# MotorController.net
KiCad netlist of a schematic drawn in EAGLE
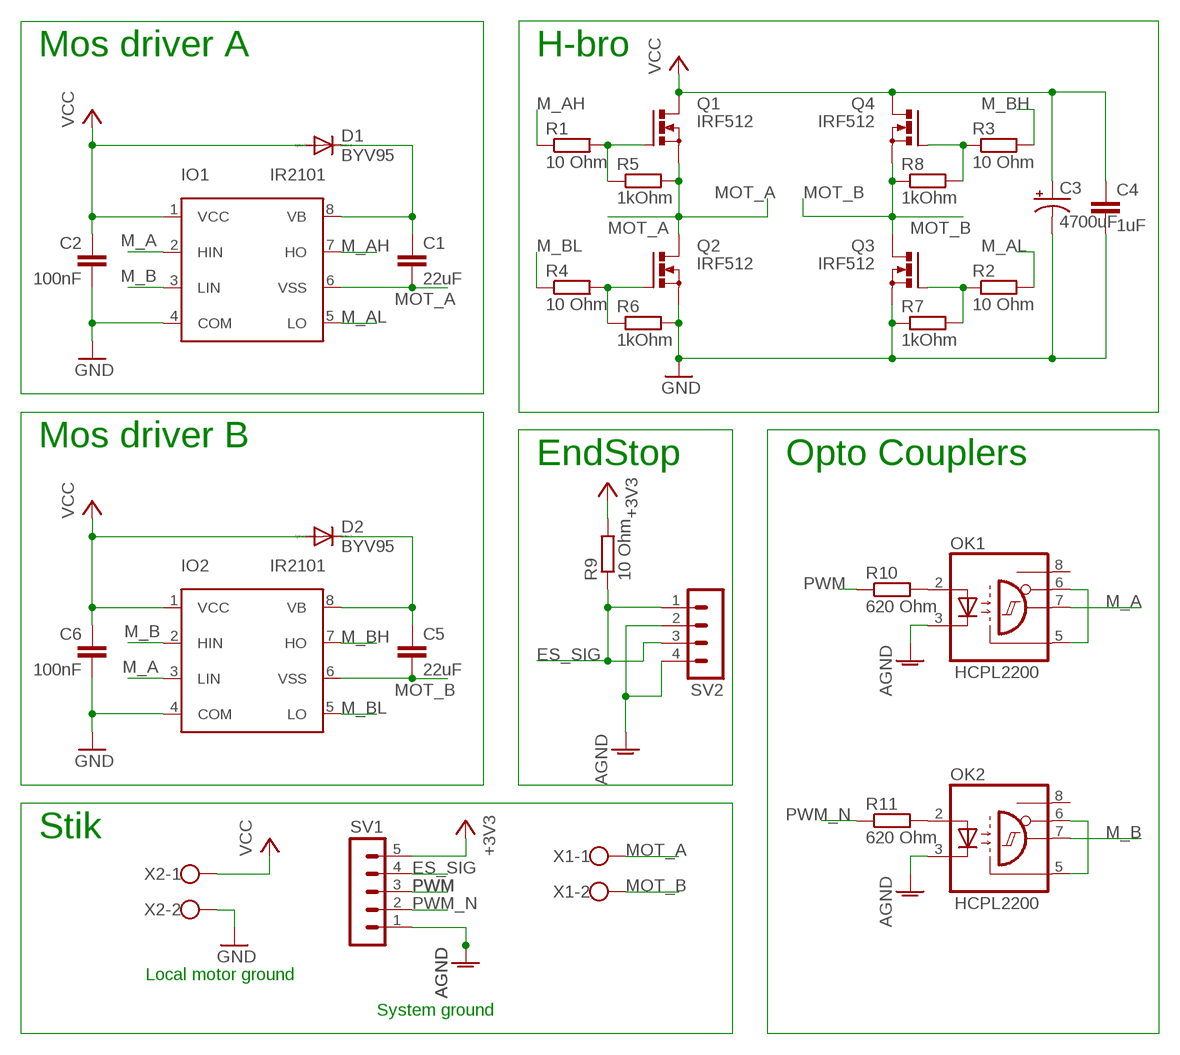
[diagram p0: schematic, sheet 1]

(export (version "E")
  (design (tool "Eeschema 10.0.6"))
  (components
    (comp (ref "C1")
      (value "22uF")
      (footprint "eagle-import:CAP-PTH-5MM")
      (libsource (lib "eagle-import") (part "CAPPTH1"))
    )
    (comp (ref "C2")
      (value "100nF")
      (footprint "eagle-import:CAP-PTH-5MM")
      (libsource (lib "eagle-import") (part "CAPPTH1"))
    )
    (comp (ref "C3")
      (value "4700uF")
      (footprint "eagle-import:CPOL-RADIAL-1000UF-25V")
      (libsource (lib "eagle-import") (part "CAP_POLPTH4"))
    )
    (comp (ref "C4")
      (value "1uF")
      (footprint "eagle-import:CAP-PTH-5MM")
      (libsource (lib "eagle-import") (part "CAPPTH1"))
    )
    (comp (ref "C5")
      (value "22uF")
      (footprint "eagle-import:CAP-PTH-5MM")
      (libsource (lib "eagle-import") (part "CAPPTH1"))
    )
    (comp (ref "C6")
      (value "100nF")
      (footprint "eagle-import:CAP-PTH-5MM")
      (libsource (lib "eagle-import") (part "CAPPTH1"))
    )
    (comp (ref "D1")
      (value "BYV95")
      (footprint "eagle-import:SOD57-10")
      (libsource (lib "eagle-import") (part "BYV95"))
    )
    (comp (ref "D2")
      (value "BYV95")
      (footprint "eagle-import:SOD57-10")
      (libsource (lib "eagle-import") (part "BYV95"))
    )
    (comp (ref "IO1")
      (value "IR2101")
      (footprint "eagle-import:DIL08")
      (libsource (lib "eagle-import") (part "IR2101"))
    )
    (comp (ref "IO2")
      (value "IR2101")
      (footprint "eagle-import:DIL08")
      (libsource (lib "eagle-import") (part "IR2101"))
    )
    (comp (ref "OK1")
      (value "HCPL2200")
      (footprint "eagle-import:DIL08")
      (fields (field (name "MF") "AGILENT TECHNOLOGIES") (field (name "MPN") "HCPL-2200"))
      (libsource (lib "eagle-import") (part "HCPL2200"))
    )
    (comp (ref "OK2")
      (value "HCPL2200")
      (footprint "eagle-import:DIL08")
      (fields (field (name "MF") "AGILENT TECHNOLOGIES") (field (name "MPN") "HCPL-2200"))
      (libsource (lib "eagle-import") (part "HCPL2200"))
    )
    (comp (ref "Q1")
      (value "IRF512")
      (footprint "eagle-import:TO220BV")
      (libsource (lib "eagle-import") (part "IRF512"))
    )
    (comp (ref "Q2")
      (value "IRF512")
      (footprint "eagle-import:TO220BV")
      (libsource (lib "eagle-import") (part "IRF512"))
    )
    (comp (ref "Q3")
      (value "IRF512")
      (footprint "eagle-import:TO220BV")
      (libsource (lib "eagle-import") (part "IRF512"))
    )
    (comp (ref "Q4")
      (value "IRF512")
      (footprint "eagle-import:TO220BV")
      (libsource (lib "eagle-import") (part "IRF512"))
    )
    (comp (ref "R1")
      (value "10 Ohm")
      (footprint "eagle-import:0207_10")
      (libsource (lib "eagle-import") (part "R-EU_0207/10"))
    )
    (comp (ref "R2")
      (value "10 Ohm")
      (footprint "eagle-import:0207_10")
      (libsource (lib "eagle-import") (part "R-EU_0207/10"))
    )
    (comp (ref "R3")
      (value "10 Ohm")
      (footprint "eagle-import:0207_10")
      (libsource (lib "eagle-import") (part "R-EU_0207/10"))
    )
    (comp (ref "R4")
      (value "10 Ohm")
      (footprint "eagle-import:0207_10")
      (libsource (lib "eagle-import") (part "R-EU_0207/10"))
    )
    (comp (ref "R5")
      (value "1kOhm")
      (footprint "eagle-import:0207_10")
      (libsource (lib "eagle-import") (part "R-EU_0207/10"))
    )
    (comp (ref "R6")
      (value "1kOhm")
      (footprint "eagle-import:0207_10")
      (libsource (lib "eagle-import") (part "R-EU_0207/10"))
    )
    (comp (ref "R7")
      (value "1kOhm")
      (footprint "eagle-import:0207_10")
      (libsource (lib "eagle-import") (part "R-EU_0207/10"))
    )
    (comp (ref "R8")
      (value "1kOhm")
      (footprint "eagle-import:0207_10")
      (libsource (lib "eagle-import") (part "R-EU_0207/10"))
    )
    (comp (ref "R9")
      (value "10 Ohm")
      (footprint "eagle-import:0207_10")
      (libsource (lib "eagle-import") (part "R-EU_0207/10"))
    )
    (comp (ref "R10")
      (value "620 Ohm")
      (footprint "eagle-import:0207_10")
      (libsource (lib "eagle-import") (part "R-EU_0207/10"))
    )
    (comp (ref "R11")
      (value "620 Ohm")
      (footprint "eagle-import:0207_10")
      (libsource (lib "eagle-import") (part "R-EU_0207/10"))
    )
    (comp (ref "SV1")
      (value "MA05-1")
      (footprint "eagle-import:MA05-1")
      (libsource (lib "eagle-import") (part "MA05-1"))
    )
    (comp (ref "SV2")
      (value "MA04-1")
      (footprint "eagle-import:MA04-1")
      (libsource (lib "eagle-import") (part "MA04-1"))
    )
    (comp (ref "X1")
      (value "W237-102")
      (footprint "eagle-import:W237-102")
      (fields (field (name "MPN") "237-102"))
      (libsource (lib "eagle-import") (part "W237-102"))
    )
    (comp (ref "X2")
      (value "W237-102")
      (footprint "eagle-import:W237-102")
      (fields (field (name "MPN") "237-102"))
      (libsource (lib "eagle-import") (part "W237-102"))
    )
  )
  (nets
    (net (code "1") (name "+3V3") (class "Default")
      (node (ref "R9") (pin "2") (pinfunction "2_2") (pintype "passive"))
      (node (ref "SV1") (pin "5") (pinfunction "5_5") (pintype "passive"))
    )
    (net (code "2") (name "/ES_SIG") (class "Default")
      (node (ref "R9") (pin "1") (pinfunction "1_1") (pintype "passive"))
      (node (ref "SV1") (pin "4") (pinfunction "4_4") (pintype "passive"))
      (node (ref "SV2") (pin "1") (pinfunction "1_1") (pintype "passive"))
      (node (ref "SV2") (pin "3") (pinfunction "3_3") (pintype "passive"))
    )
    (net (code "3") (name "/MOT_A") (class "Default")
      (node (ref "C1") (pin "2") (pinfunction "2_2") (pintype "passive"))
      (node (ref "IO1") (pin "6") (pinfunction "VSS_6") (pintype "bidirectional"))
      (node (ref "Q1") (pin "S") (pinfunction "S_S") (pintype "passive"))
      (node (ref "Q2") (pin "D") (pinfunction "D_D") (pintype "passive"))
      (node (ref "R5") (pin "2") (pinfunction "2_2") (pintype "passive"))
      (node (ref "X1") (pin "1") (pinfunction "KL_1") (pintype "passive"))
    )
    (net (code "4") (name "/MOT_B") (class "Default")
      (node (ref "C5") (pin "2") (pinfunction "2_2") (pintype "passive"))
      (node (ref "IO2") (pin "6") (pinfunction "VSS_6") (pintype "bidirectional"))
      (node (ref "Q3") (pin "D") (pinfunction "D_D") (pintype "passive"))
      (node (ref "Q4") (pin "S") (pinfunction "S_S") (pintype "passive"))
      (node (ref "R8") (pin "1") (pinfunction "1_1") (pintype "passive"))
      (node (ref "X1") (pin "2") (pinfunction "KL_2") (pintype "passive"))
    )
    (net (code "5") (name "/M_A") (class "Default")
      (node (ref "IO1") (pin "2") (pinfunction "HIN_2") (pintype "bidirectional"))
      (node (ref "IO2") (pin "3") (pinfunction "LIN_3") (pintype "bidirectional"))
      (node (ref "OK1") (pin "7") (pinfunction "VO_7") (pintype "passive"))
    )
    (net (code "6") (name "/M_AH") (class "Default")
      (node (ref "IO1") (pin "7") (pinfunction "HO_7") (pintype "bidirectional"))
      (node (ref "R1") (pin "1") (pinfunction "1_1") (pintype "passive"))
    )
    (net (code "7") (name "/M_AL") (class "Default")
      (node (ref "IO1") (pin "5") (pinfunction "LO_5") (pintype "bidirectional"))
      (node (ref "R2") (pin "2") (pinfunction "2_2") (pintype "passive"))
    )
    (net (code "8") (name "/M_B") (class "Default")
      (node (ref "IO1") (pin "3") (pinfunction "LIN_3") (pintype "bidirectional"))
      (node (ref "IO2") (pin "2") (pinfunction "HIN_2") (pintype "bidirectional"))
      (node (ref "OK2") (pin "7") (pinfunction "VO_7") (pintype "passive"))
    )
    (net (code "9") (name "/M_BH") (class "Default")
      (node (ref "IO2") (pin "7") (pinfunction "HO_7") (pintype "bidirectional"))
      (node (ref "R3") (pin "2") (pinfunction "2_2") (pintype "passive"))
    )
    (net (code "10") (name "/M_BL") (class "Default")
      (node (ref "IO2") (pin "5") (pinfunction "LO_5") (pintype "bidirectional"))
      (node (ref "R4") (pin "1") (pinfunction "1_1") (pintype "passive"))
    )
    (net (code "11") (name "/PWM") (class "Default")
      (node (ref "R10") (pin "1") (pinfunction "1_1") (pintype "passive"))
      (node (ref "SV1") (pin "3") (pinfunction "3_3") (pintype "passive"))
    )
    (net (code "12") (name "/PWM_N") (class "Default")
      (node (ref "R11") (pin "1") (pinfunction "1_1") (pintype "passive"))
      (node (ref "SV1") (pin "2") (pinfunction "2_2") (pintype "passive"))
    )
    (net (code "13") (name "AGND") (class "Default")
      (node (ref "OK1") (pin "3") (pinfunction "C_3") (pintype "passive"))
      (node (ref "OK2") (pin "3") (pinfunction "C_3") (pintype "passive"))
      (node (ref "SV1") (pin "1") (pinfunction "1_1") (pintype "passive"))
      (node (ref "SV2") (pin "2") (pinfunction "2_2") (pintype "passive"))
      (node (ref "SV2") (pin "4") (pinfunction "4_4") (pintype "passive"))
    )
    (net (code "14") (name "GND") (class "Default")
      (node (ref "C2") (pin "2") (pinfunction "2_2") (pintype "passive"))
      (node (ref "C3") (pin "2") (pinfunction "-_2") (pintype "passive"))
      (node (ref "C4") (pin "2") (pinfunction "2_2") (pintype "passive"))
      (node (ref "C6") (pin "2") (pinfunction "2_2") (pintype "passive"))
      (node (ref "IO1") (pin "4") (pinfunction "COM_4") (pintype "bidirectional"))
      (node (ref "IO2") (pin "4") (pinfunction "COM_4") (pintype "bidirectional"))
      (node (ref "Q2") (pin "S") (pinfunction "S_S") (pintype "passive"))
      (node (ref "Q3") (pin "S") (pinfunction "S_S") (pintype "passive"))
      (node (ref "R6") (pin "2") (pinfunction "2_2") (pintype "passive"))
      (node (ref "R7") (pin "1") (pinfunction "1_1") (pintype "passive"))
      (node (ref "X2") (pin "2") (pinfunction "KL_2") (pintype "passive"))
    )
    (net (code "15") (name "Net-(IO1-VB)") (class "Default")
      (node (ref "C1") (pin "1") (pinfunction "1_1") (pintype "passive"))
      (node (ref "D1") (pin "C") (pinfunction "C_C") (pintype "passive"))
      (node (ref "IO1") (pin "8") (pinfunction "VB_8") (pintype "bidirectional"))
    )
    (net (code "16") (name "Net-(IO2-VB)") (class "Default")
      (node (ref "C5") (pin "1") (pinfunction "1_1") (pintype "passive"))
      (node (ref "D2") (pin "C") (pinfunction "C_C") (pintype "passive"))
      (node (ref "IO2") (pin "8") (pinfunction "VB_8") (pintype "bidirectional"))
    )
    (net (code "17") (name "Net-(OK1-A)") (class "Default")
      (node (ref "OK1") (pin "2") (pinfunction "A_2") (pintype "passive"))
      (node (ref "R10") (pin "2") (pinfunction "2_2") (pintype "passive"))
    )
    (net (code "18") (name "Net-(OK1-GND)") (class "Default")
      (node (ref "OK1") (pin "5") (pinfunction "GND_5") (pintype "passive"))
      (node (ref "OK1") (pin "6") (pinfunction "VE_6") (pintype "passive"))
    )
    (net (code "19") (name "Net-(OK2-A)") (class "Default")
      (node (ref "OK2") (pin "2") (pinfunction "A_2") (pintype "passive"))
      (node (ref "R11") (pin "2") (pinfunction "2_2") (pintype "passive"))
    )
    (net (code "20") (name "Net-(OK2-GND)") (class "Default")
      (node (ref "OK2") (pin "5") (pinfunction "GND_5") (pintype "passive"))
      (node (ref "OK2") (pin "6") (pinfunction "VE_6") (pintype "passive"))
    )
    (net (code "21") (name "Net-(Q1-PadG)") (class "Default")
      (node (ref "Q1") (pin "G") (pinfunction "G_G") (pintype "passive"))
      (node (ref "R1") (pin "2") (pinfunction "2_2") (pintype "passive"))
      (node (ref "R5") (pin "1") (pinfunction "1_1") (pintype "passive"))
    )
    (net (code "22") (name "Net-(Q2-PadG)") (class "Default")
      (node (ref "Q2") (pin "G") (pinfunction "G_G") (pintype "passive"))
      (node (ref "R4") (pin "2") (pinfunction "2_2") (pintype "passive"))
      (node (ref "R6") (pin "1") (pinfunction "1_1") (pintype "passive"))
    )
    (net (code "23") (name "Net-(Q3-PadG)") (class "Default")
      (node (ref "Q3") (pin "G") (pinfunction "G_G") (pintype "passive"))
      (node (ref "R2") (pin "1") (pinfunction "1_1") (pintype "passive"))
      (node (ref "R7") (pin "2") (pinfunction "2_2") (pintype "passive"))
    )
    (net (code "24") (name "Net-(Q4-PadG)") (class "Default")
      (node (ref "Q4") (pin "G") (pinfunction "G_G") (pintype "passive"))
      (node (ref "R3") (pin "1") (pinfunction "1_1") (pintype "passive"))
      (node (ref "R8") (pin "2") (pinfunction "2_2") (pintype "passive"))
    )
    (net (code "25") (name "VCC") (class "Default")
      (node (ref "C2") (pin "1") (pinfunction "1_1") (pintype "passive"))
      (node (ref "C3") (pin "1") (pinfunction "+_1") (pintype "passive"))
      (node (ref "C4") (pin "1") (pinfunction "1_1") (pintype "passive"))
      (node (ref "C6") (pin "1") (pinfunction "1_1") (pintype "passive"))
      (node (ref "D1") (pin "A") (pinfunction "A_A") (pintype "passive"))
      (node (ref "D2") (pin "A") (pinfunction "A_A") (pintype "passive"))
      (node (ref "IO1") (pin "1") (pinfunction "VCC_1") (pintype "bidirectional"))
      (node (ref "IO2") (pin "1") (pinfunction "VCC_1") (pintype "bidirectional"))
      (node (ref "Q1") (pin "D") (pinfunction "D_D") (pintype "passive"))
      (node (ref "Q4") (pin "D") (pinfunction "D_D") (pintype "passive"))
      (node (ref "X2") (pin "1") (pinfunction "KL_1") (pintype "passive"))
    )
    (net (code "26") (name "unconnected-(OK1-VCC-Pad8)") (class "Default")
      (node (ref "OK1") (pin "8") (pinfunction "VCC_8") (pintype "passive"))
    )
    (net (code "27") (name "unconnected-(OK2-VCC-Pad8)") (class "Default")
      (node (ref "OK2") (pin "8") (pinfunction "VCC_8") (pintype "passive"))
    )
  )
)
